# 5MMHexaStellaBreakout.net
KiCad netlist of a schematic drawn in EAGLE
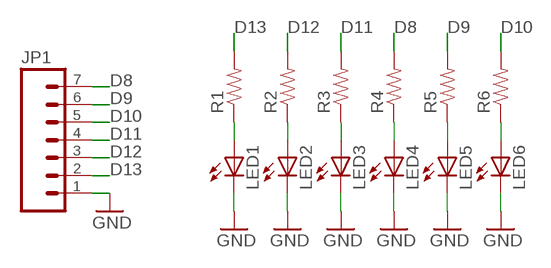
[diagram p0: schematic, sheet 1]

(export (version "E")
  (design (tool "Eeschema 10.0.6"))
  (components
    (comp (ref "JP1")
      (value "M07")
      (footprint "eagle-import:1X07")
      (libsource (lib "eagle-import") (part "M07"))
    )
    (comp (ref "LED1")
      (value "LED5MM")
      (footprint "eagle-import:LED5MM")
      (libsource (lib "eagle-import") (part "LED5MM"))
    )
    (comp (ref "LED2")
      (value "LED5MM")
      (footprint "eagle-import:LED5MM")
      (libsource (lib "eagle-import") (part "LED5MM"))
    )
    (comp (ref "LED3")
      (value "LED5MM")
      (footprint "eagle-import:LED5MM")
      (libsource (lib "eagle-import") (part "LED5MM"))
    )
    (comp (ref "LED4")
      (value "LED5MM")
      (footprint "eagle-import:LED5MM")
      (libsource (lib "eagle-import") (part "LED5MM"))
    )
    (comp (ref "LED5")
      (value "LED5MM")
      (footprint "eagle-import:LED5MM")
      (libsource (lib "eagle-import") (part "LED5MM"))
    )
    (comp (ref "LED6")
      (value "LED5MM")
      (footprint "eagle-import:LED5MM")
      (libsource (lib "eagle-import") (part "LED5MM"))
    )
    (comp (ref "R1")
      (value "RESISTORAXIAL-0.3")
      (footprint "eagle-import:AXIAL-0.3")
      (libsource (lib "eagle-import") (part "RESISTORAXIAL-0.3"))
    )
    (comp (ref "R2")
      (value "RESISTORAXIAL-0.3")
      (footprint "eagle-import:AXIAL-0.3")
      (libsource (lib "eagle-import") (part "RESISTORAXIAL-0.3"))
    )
    (comp (ref "R3")
      (value "RESISTORAXIAL-0.3")
      (footprint "eagle-import:AXIAL-0.3")
      (libsource (lib "eagle-import") (part "RESISTORAXIAL-0.3"))
    )
    (comp (ref "R4")
      (value "RESISTORAXIAL-0.3")
      (footprint "eagle-import:AXIAL-0.3")
      (libsource (lib "eagle-import") (part "RESISTORAXIAL-0.3"))
    )
    (comp (ref "R5")
      (value "RESISTORAXIAL-0.3")
      (footprint "eagle-import:AXIAL-0.3")
      (libsource (lib "eagle-import") (part "RESISTORAXIAL-0.3"))
    )
    (comp (ref "R6")
      (value "RESISTORAXIAL-0.3")
      (footprint "eagle-import:AXIAL-0.3")
      (libsource (lib "eagle-import") (part "RESISTORAXIAL-0.3"))
    )
  )
  (nets
    (net (code "1") (name "/D8") (class "Default")
      (node (ref "JP1") (pin "7") (pinfunction "7_7") (pintype "passive"))
      (node (ref "R4") (pin "P$2") (pinfunction "2_P$2") (pintype "passive"))
    )
    (net (code "2") (name "/D9") (class "Default")
      (node (ref "JP1") (pin "6") (pinfunction "6_6") (pintype "passive"))
      (node (ref "R5") (pin "P$2") (pinfunction "2_P$2") (pintype "passive"))
    )
    (net (code "3") (name "/D10") (class "Default")
      (node (ref "JP1") (pin "5") (pinfunction "5_5") (pintype "passive"))
      (node (ref "R6") (pin "P$2") (pinfunction "2_P$2") (pintype "passive"))
    )
    (net (code "4") (name "/D11") (class "Default")
      (node (ref "JP1") (pin "4") (pinfunction "4_4") (pintype "passive"))
      (node (ref "R3") (pin "P$2") (pinfunction "2_P$2") (pintype "passive"))
    )
    (net (code "5") (name "/D12") (class "Default")
      (node (ref "JP1") (pin "3") (pinfunction "3_3") (pintype "passive"))
      (node (ref "R2") (pin "P$2") (pinfunction "2_P$2") (pintype "passive"))
    )
    (net (code "6") (name "/D13") (class "Default")
      (node (ref "JP1") (pin "2") (pinfunction "2_2") (pintype "passive"))
      (node (ref "R1") (pin "P$2") (pinfunction "2_P$2") (pintype "passive"))
    )
    (net (code "7") (name "GND") (class "Default")
      (node (ref "JP1") (pin "1") (pinfunction "1_1") (pintype "passive"))
      (node (ref "LED1") (pin "K") (pinfunction "C_K") (pintype "passive"))
      (node (ref "LED2") (pin "K") (pinfunction "C_K") (pintype "passive"))
      (node (ref "LED3") (pin "K") (pinfunction "C_K") (pintype "passive"))
      (node (ref "LED4") (pin "K") (pinfunction "C_K") (pintype "passive"))
      (node (ref "LED5") (pin "K") (pinfunction "C_K") (pintype "passive"))
      (node (ref "LED6") (pin "K") (pinfunction "C_K") (pintype "passive"))
    )
    (net (code "8") (name "Net-(R1-1)") (class "Default")
      (node (ref "LED1") (pin "A") (pinfunction "A_A") (pintype "passive"))
      (node (ref "R1") (pin "P$1") (pinfunction "1_P$1") (pintype "passive"))
    )
    (net (code "9") (name "Net-(R2-1)") (class "Default")
      (node (ref "LED2") (pin "A") (pinfunction "A_A") (pintype "passive"))
      (node (ref "R2") (pin "P$1") (pinfunction "1_P$1") (pintype "passive"))
    )
    (net (code "10") (name "Net-(R3-1)") (class "Default")
      (node (ref "LED3") (pin "A") (pinfunction "A_A") (pintype "passive"))
      (node (ref "R3") (pin "P$1") (pinfunction "1_P$1") (pintype "passive"))
    )
    (net (code "11") (name "Net-(R4-1)") (class "Default")
      (node (ref "LED4") (pin "A") (pinfunction "A_A") (pintype "passive"))
      (node (ref "R4") (pin "P$1") (pinfunction "1_P$1") (pintype "passive"))
    )
    (net (code "12") (name "Net-(R5-1)") (class "Default")
      (node (ref "LED5") (pin "A") (pinfunction "A_A") (pintype "passive"))
      (node (ref "R5") (pin "P$1") (pinfunction "1_P$1") (pintype "passive"))
    )
    (net (code "13") (name "Net-(R6-1)") (class "Default")
      (node (ref "LED6") (pin "A") (pinfunction "A_A") (pintype "passive"))
      (node (ref "R6") (pin "P$1") (pinfunction "1_P$1") (pintype "passive"))
    )
  )
)
